# SCH_QLC_CONNECTOR_2023-04-06.net
KiCad netlist of a schematic drawn in EasyEDA
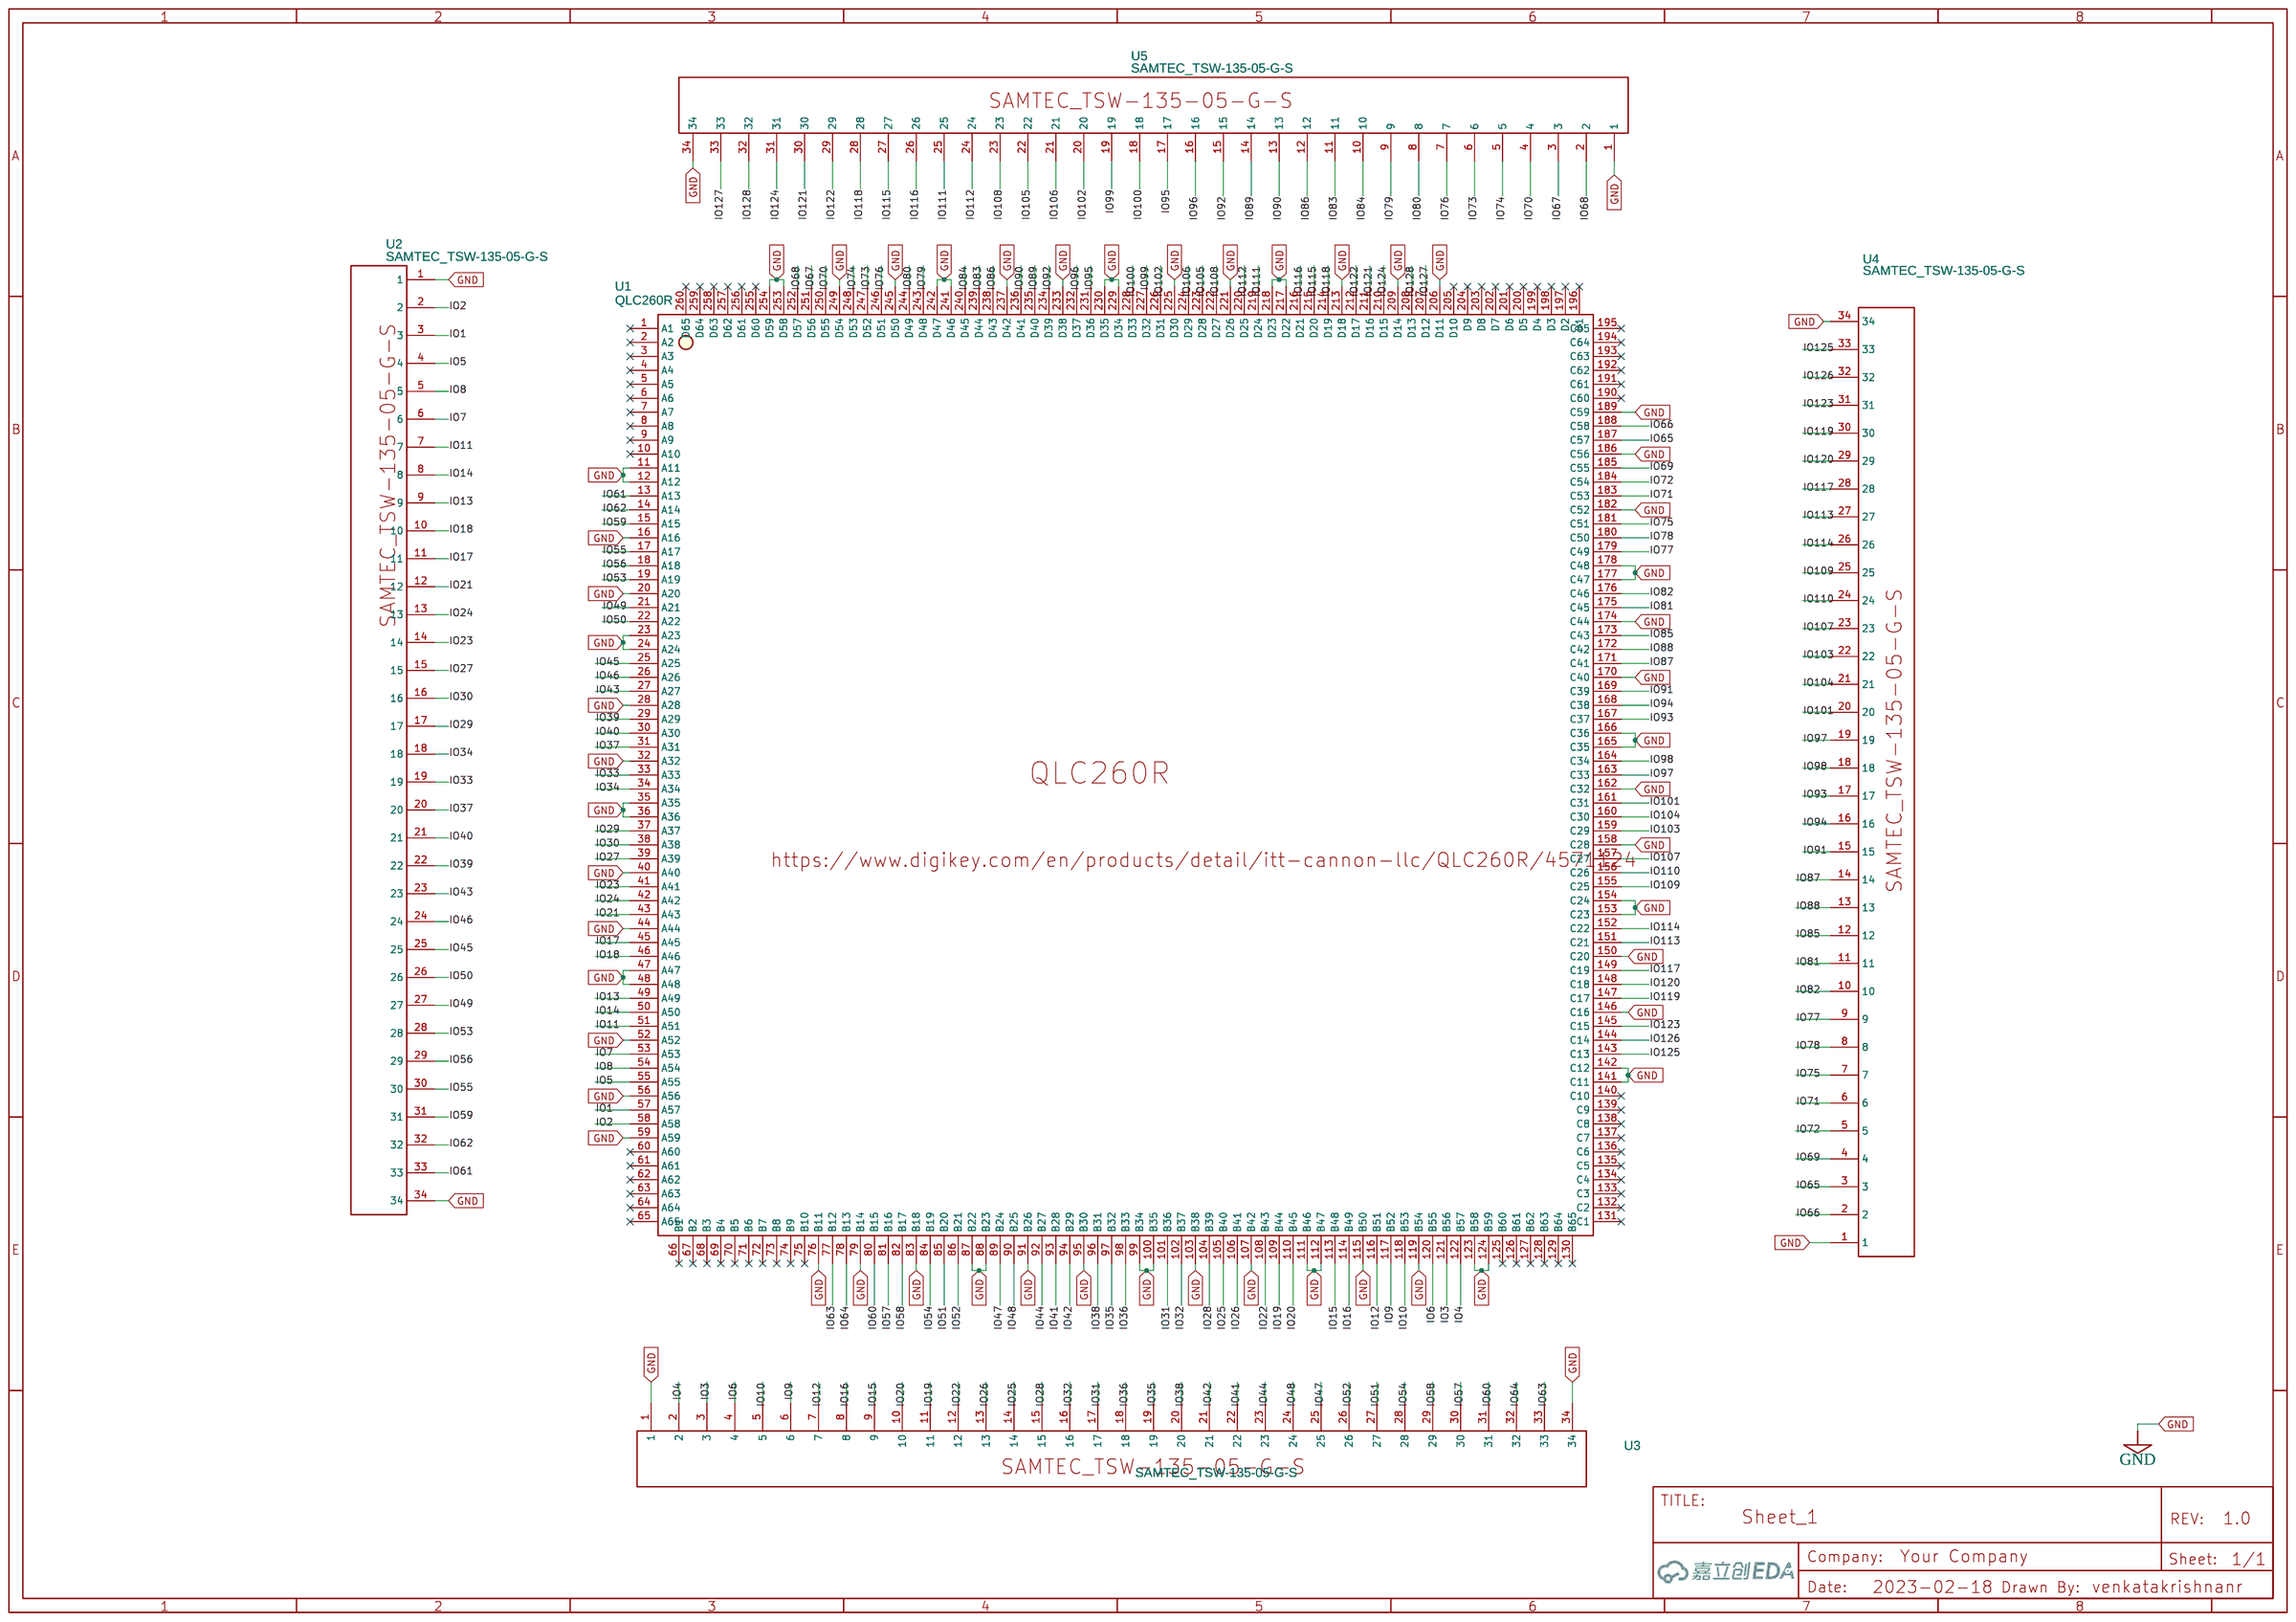
[diagram p0: schematic sheet]

(export (version "E")
  (design (tool "Eeschema 10.0.6"))
  (components
    (comp (ref "U1")
      (value "QLC260R")
      (fields (field (name "BOM_Supplier Part") "1003-2400-ND"))
      (libsource (lib "") (part "QLC260R"))
    )
    (comp (ref "U2")
      (value "SAMTEC_TSW-135-05-G-S")
      (fields
        (field (name "BOM_Manufacturer Part") "TSW-135-05-G-S")
        (field (name "BOM_Supplier Part") "SAM1013-35-ND")
      )
      (libsource (lib "") (part "SAMTEC_TSW-135-05-G-S_1"))
    )
    (comp (ref "U3")
      (value "SAMTEC_TSW-135-05-G-S")
      (fields
        (field (name "BOM_Manufacturer Part") "TSW-135-05-G-S")
        (field (name "BOM_Supplier Part") "SAM1013-35-ND")
      )
      (libsource (lib "") (part "SAMTEC_TSW-135-05-G-S"))
    )
    (comp (ref "U4")
      (value "SAMTEC_TSW-135-05-G-S")
      (fields
        (field (name "BOM_Manufacturer Part") "TSW-135-05-G-S")
        (field (name "BOM_Supplier Part") "SAM1013-35-ND")
      )
      (libsource (lib "") (part "SAMTEC_TSW-135-05-G-S_2"))
    )
    (comp (ref "U5")
      (value "SAMTEC_TSW-135-05-G-S")
      (fields
        (field (name "BOM_Manufacturer Part") "TSW-135-05-G-S")
        (field (name "BOM_Supplier Part") "SAM1013-35-ND")
      )
      (libsource (lib "") (part "SAMTEC_TSW-135-05-G-S_3"))
    )
  )
  (nets
    (net (code "1") (name "/IO1") (class "Default")
      (node (ref "U1") (pin "57") (pinfunction "A57_57") (pintype "unspecified"))
      (node (ref "U2") (pin "3") (pinfunction "3_3") (pintype "unspecified"))
    )
    (net (code "2") (name "/IO2") (class "Default")
      (node (ref "U1") (pin "58") (pinfunction "A58_58") (pintype "unspecified"))
      (node (ref "U2") (pin "2") (pinfunction "2_2") (pintype "unspecified"))
    )
    (net (code "3") (name "/IO3") (class "Default")
      (node (ref "U1") (pin "121") (pinfunction "B56_121") (pintype "unspecified"))
      (node (ref "U3") (pin "3") (pinfunction "3_3") (pintype "unspecified"))
    )
    (net (code "4") (name "/IO4") (class "Default")
      (node (ref "U1") (pin "122") (pinfunction "B57_122") (pintype "unspecified"))
      (node (ref "U3") (pin "2") (pinfunction "2_2") (pintype "unspecified"))
    )
    (net (code "5") (name "/IO5") (class "Default")
      (node (ref "U1") (pin "55") (pinfunction "A55_55") (pintype "unspecified"))
      (node (ref "U2") (pin "4") (pinfunction "4_4") (pintype "unspecified"))
    )
    (net (code "6") (name "/IO6") (class "Default")
      (node (ref "U1") (pin "120") (pinfunction "B55_120") (pintype "unspecified"))
      (node (ref "U3") (pin "4") (pinfunction "4_4") (pintype "unspecified"))
    )
    (net (code "7") (name "/IO7") (class "Default")
      (node (ref "U1") (pin "53") (pinfunction "A53_53") (pintype "unspecified"))
      (node (ref "U2") (pin "6") (pinfunction "6_6") (pintype "unspecified"))
    )
    (net (code "8") (name "/IO8") (class "Default")
      (node (ref "U1") (pin "54") (pinfunction "A54_54") (pintype "unspecified"))
      (node (ref "U2") (pin "5") (pinfunction "5_5") (pintype "unspecified"))
    )
    (net (code "9") (name "/IO9") (class "Default")
      (node (ref "U1") (pin "117") (pinfunction "B52_117") (pintype "unspecified"))
      (node (ref "U3") (pin "6") (pinfunction "6_6") (pintype "unspecified"))
    )
    (net (code "10") (name "/IO10") (class "Default")
      (node (ref "U1") (pin "118") (pinfunction "B53_118") (pintype "unspecified"))
      (node (ref "U3") (pin "5") (pinfunction "5_5") (pintype "unspecified"))
    )
    (net (code "11") (name "/IO11") (class "Default")
      (node (ref "U1") (pin "51") (pinfunction "A51_51") (pintype "unspecified"))
      (node (ref "U2") (pin "7") (pinfunction "7_7") (pintype "unspecified"))
    )
    (net (code "12") (name "/IO12") (class "Default")
      (node (ref "U1") (pin "116") (pinfunction "B51_116") (pintype "unspecified"))
      (node (ref "U3") (pin "7") (pinfunction "7_7") (pintype "unspecified"))
    )
    (net (code "13") (name "/IO13") (class "Default")
      (node (ref "U1") (pin "49") (pinfunction "A49_49") (pintype "unspecified"))
      (node (ref "U2") (pin "9") (pinfunction "9_9") (pintype "unspecified"))
    )
    (net (code "14") (name "/IO14") (class "Default")
      (node (ref "U1") (pin "50") (pinfunction "A50_50") (pintype "unspecified"))
      (node (ref "U2") (pin "8") (pinfunction "8_8") (pintype "unspecified"))
    )
    (net (code "15") (name "/IO15") (class "Default")
      (node (ref "U1") (pin "113") (pinfunction "B48_113") (pintype "unspecified"))
      (node (ref "U3") (pin "9") (pinfunction "9_9") (pintype "unspecified"))
    )
    (net (code "16") (name "/IO16") (class "Default")
      (node (ref "U1") (pin "114") (pinfunction "B49_114") (pintype "unspecified"))
      (node (ref "U3") (pin "8") (pinfunction "8_8") (pintype "unspecified"))
    )
    (net (code "17") (name "/IO17") (class "Default")
      (node (ref "U1") (pin "45") (pinfunction "A45_45") (pintype "unspecified"))
      (node (ref "U2") (pin "11") (pinfunction "11_11") (pintype "unspecified"))
    )
    (net (code "18") (name "/IO18") (class "Default")
      (node (ref "U1") (pin "46") (pinfunction "A46_46") (pintype "unspecified"))
      (node (ref "U2") (pin "10") (pinfunction "10_10") (pintype "unspecified"))
    )
    (net (code "19") (name "/IO19") (class "Default")
      (node (ref "U1") (pin "109") (pinfunction "B44_109") (pintype "unspecified"))
      (node (ref "U3") (pin "11") (pinfunction "11_11") (pintype "unspecified"))
    )
    (net (code "20") (name "/IO20") (class "Default")
      (node (ref "U1") (pin "110") (pinfunction "B45_110") (pintype "unspecified"))
      (node (ref "U3") (pin "10") (pinfunction "10_10") (pintype "unspecified"))
    )
    (net (code "21") (name "/IO21") (class "Default")
      (node (ref "U1") (pin "43") (pinfunction "A43_43") (pintype "unspecified"))
      (node (ref "U2") (pin "12") (pinfunction "12_12") (pintype "unspecified"))
    )
    (net (code "22") (name "/IO22") (class "Default")
      (node (ref "U1") (pin "108") (pinfunction "B43_108") (pintype "unspecified"))
      (node (ref "U3") (pin "12") (pinfunction "12_12") (pintype "unspecified"))
    )
    (net (code "23") (name "/IO23") (class "Default")
      (node (ref "U1") (pin "41") (pinfunction "A41_41") (pintype "unspecified"))
      (node (ref "U2") (pin "14") (pinfunction "14_14") (pintype "unspecified"))
    )
    (net (code "24") (name "/IO24") (class "Default")
      (node (ref "U1") (pin "42") (pinfunction "A42_42") (pintype "unspecified"))
      (node (ref "U2") (pin "13") (pinfunction "13_13") (pintype "unspecified"))
    )
    (net (code "25") (name "/IO25") (class "Default")
      (node (ref "U1") (pin "105") (pinfunction "B40_105") (pintype "unspecified"))
      (node (ref "U3") (pin "14") (pinfunction "14_14") (pintype "unspecified"))
    )
    (net (code "26") (name "/IO26") (class "Default")
      (node (ref "U1") (pin "106") (pinfunction "B41_106") (pintype "unspecified"))
      (node (ref "U3") (pin "13") (pinfunction "13_13") (pintype "unspecified"))
    )
    (net (code "27") (name "/IO27") (class "Default")
      (node (ref "U1") (pin "39") (pinfunction "A39_39") (pintype "unspecified"))
      (node (ref "U2") (pin "15") (pinfunction "15_15") (pintype "unspecified"))
    )
    (net (code "28") (name "/IO28") (class "Default")
      (node (ref "U1") (pin "104") (pinfunction "B39_104") (pintype "unspecified"))
      (node (ref "U3") (pin "15") (pinfunction "15_15") (pintype "unspecified"))
    )
    (net (code "29") (name "/IO29") (class "Default")
      (node (ref "U1") (pin "37") (pinfunction "A37_37") (pintype "unspecified"))
      (node (ref "U2") (pin "17") (pinfunction "17_17") (pintype "unspecified"))
    )
    (net (code "30") (name "/IO30") (class "Default")
      (node (ref "U1") (pin "38") (pinfunction "A38_38") (pintype "unspecified"))
      (node (ref "U2") (pin "16") (pinfunction "16_16") (pintype "unspecified"))
    )
    (net (code "31") (name "/IO31") (class "Default")
      (node (ref "U1") (pin "101") (pinfunction "B36_101") (pintype "unspecified"))
      (node (ref "U3") (pin "17") (pinfunction "17_17") (pintype "unspecified"))
    )
    (net (code "32") (name "/IO32") (class "Default")
      (node (ref "U1") (pin "102") (pinfunction "B37_102") (pintype "unspecified"))
      (node (ref "U3") (pin "16") (pinfunction "16_16") (pintype "unspecified"))
    )
    (net (code "33") (name "/IO33") (class "Default")
      (node (ref "U1") (pin "33") (pinfunction "A33_33") (pintype "unspecified"))
      (node (ref "U2") (pin "19") (pinfunction "19_19") (pintype "unspecified"))
    )
    (net (code "34") (name "/IO34") (class "Default")
      (node (ref "U1") (pin "34") (pinfunction "A34_34") (pintype "unspecified"))
      (node (ref "U2") (pin "18") (pinfunction "18_18") (pintype "unspecified"))
    )
    (net (code "35") (name "/IO35") (class "Default")
      (node (ref "U1") (pin "97") (pinfunction "B32_97") (pintype "unspecified"))
      (node (ref "U3") (pin "19") (pinfunction "19_19") (pintype "unspecified"))
    )
    (net (code "36") (name "/IO36") (class "Default")
      (node (ref "U1") (pin "98") (pinfunction "B33_98") (pintype "unspecified"))
      (node (ref "U3") (pin "18") (pinfunction "18_18") (pintype "unspecified"))
    )
    (net (code "37") (name "/IO37") (class "Default")
      (node (ref "U1") (pin "31") (pinfunction "A31_31") (pintype "unspecified"))
      (node (ref "U2") (pin "20") (pinfunction "20_20") (pintype "unspecified"))
    )
    (net (code "38") (name "/IO38") (class "Default")
      (node (ref "U1") (pin "96") (pinfunction "B31_96") (pintype "unspecified"))
      (node (ref "U3") (pin "20") (pinfunction "20_20") (pintype "unspecified"))
    )
    (net (code "39") (name "/IO39") (class "Default")
      (node (ref "U1") (pin "29") (pinfunction "A29_29") (pintype "unspecified"))
      (node (ref "U2") (pin "22") (pinfunction "22_22") (pintype "unspecified"))
    )
    (net (code "40") (name "/IO40") (class "Default")
      (node (ref "U1") (pin "30") (pinfunction "A30_30") (pintype "unspecified"))
      (node (ref "U2") (pin "21") (pinfunction "21_21") (pintype "unspecified"))
    )
    (net (code "41") (name "/IO41") (class "Default")
      (node (ref "U1") (pin "93") (pinfunction "B28_93") (pintype "unspecified"))
      (node (ref "U3") (pin "22") (pinfunction "22_22") (pintype "unspecified"))
    )
    (net (code "42") (name "/IO42") (class "Default")
      (node (ref "U1") (pin "94") (pinfunction "B29_94") (pintype "unspecified"))
      (node (ref "U3") (pin "21") (pinfunction "21_21") (pintype "unspecified"))
    )
    (net (code "43") (name "/IO43") (class "Default")
      (node (ref "U1") (pin "27") (pinfunction "A27_27") (pintype "unspecified"))
      (node (ref "U2") (pin "23") (pinfunction "23_23") (pintype "unspecified"))
    )
    (net (code "44") (name "/IO44") (class "Default")
      (node (ref "U1") (pin "92") (pinfunction "B27_92") (pintype "unspecified"))
      (node (ref "U3") (pin "23") (pinfunction "23_23") (pintype "unspecified"))
    )
    (net (code "45") (name "/IO45") (class "Default")
      (node (ref "U1") (pin "25") (pinfunction "A25_25") (pintype "unspecified"))
      (node (ref "U2") (pin "25") (pinfunction "25_25") (pintype "unspecified"))
    )
    (net (code "46") (name "/IO46") (class "Default")
      (node (ref "U1") (pin "26") (pinfunction "A26_26") (pintype "unspecified"))
      (node (ref "U2") (pin "24") (pinfunction "24_24") (pintype "unspecified"))
    )
    (net (code "47") (name "/IO47") (class "Default")
      (node (ref "U1") (pin "89") (pinfunction "B24_89") (pintype "unspecified"))
      (node (ref "U3") (pin "25") (pinfunction "25_25") (pintype "unspecified"))
    )
    (net (code "48") (name "/IO48") (class "Default")
      (node (ref "U1") (pin "90") (pinfunction "B25_90") (pintype "unspecified"))
      (node (ref "U3") (pin "24") (pinfunction "24_24") (pintype "unspecified"))
    )
    (net (code "49") (name "/IO49") (class "Default")
      (node (ref "U1") (pin "21") (pinfunction "A21_21") (pintype "unspecified"))
      (node (ref "U2") (pin "27") (pinfunction "27_27") (pintype "unspecified"))
    )
    (net (code "50") (name "/IO50") (class "Default")
      (node (ref "U1") (pin "22") (pinfunction "A22_22") (pintype "unspecified"))
      (node (ref "U2") (pin "26") (pinfunction "26_26") (pintype "unspecified"))
    )
    (net (code "51") (name "/IO51") (class "Default")
      (node (ref "U1") (pin "85") (pinfunction "B20_85") (pintype "unspecified"))
      (node (ref "U3") (pin "27") (pinfunction "27_27") (pintype "unspecified"))
    )
    (net (code "52") (name "/IO52") (class "Default")
      (node (ref "U1") (pin "86") (pinfunction "B21_86") (pintype "unspecified"))
      (node (ref "U3") (pin "26") (pinfunction "26_26") (pintype "unspecified"))
    )
    (net (code "53") (name "/IO53") (class "Default")
      (node (ref "U1") (pin "19") (pinfunction "A19_19") (pintype "unspecified"))
      (node (ref "U2") (pin "28") (pinfunction "28_28") (pintype "unspecified"))
    )
    (net (code "54") (name "/IO54") (class "Default")
      (node (ref "U1") (pin "84") (pinfunction "B19_84") (pintype "unspecified"))
      (node (ref "U3") (pin "28") (pinfunction "28_28") (pintype "unspecified"))
    )
    (net (code "55") (name "/IO55") (class "Default")
      (node (ref "U1") (pin "17") (pinfunction "A17_17") (pintype "unspecified"))
      (node (ref "U2") (pin "30") (pinfunction "30_30") (pintype "unspecified"))
    )
    (net (code "56") (name "/IO56") (class "Default")
      (node (ref "U1") (pin "18") (pinfunction "A18_18") (pintype "unspecified"))
      (node (ref "U2") (pin "29") (pinfunction "29_29") (pintype "unspecified"))
    )
    (net (code "57") (name "/IO57") (class "Default")
      (node (ref "U1") (pin "81") (pinfunction "B16_81") (pintype "unspecified"))
      (node (ref "U3") (pin "30") (pinfunction "30_30") (pintype "unspecified"))
    )
    (net (code "58") (name "/IO58") (class "Default")
      (node (ref "U1") (pin "82") (pinfunction "B17_82") (pintype "unspecified"))
      (node (ref "U3") (pin "29") (pinfunction "29_29") (pintype "unspecified"))
    )
    (net (code "59") (name "/IO59") (class "Default")
      (node (ref "U1") (pin "15") (pinfunction "A15_15") (pintype "unspecified"))
      (node (ref "U2") (pin "31") (pinfunction "31_31") (pintype "unspecified"))
    )
    (net (code "60") (name "/IO60") (class "Default")
      (node (ref "U1") (pin "80") (pinfunction "B15_80") (pintype "unspecified"))
      (node (ref "U3") (pin "31") (pinfunction "31_31") (pintype "unspecified"))
    )
    (net (code "61") (name "/IO61") (class "Default")
      (node (ref "U1") (pin "13") (pinfunction "A13_13") (pintype "unspecified"))
      (node (ref "U2") (pin "33") (pinfunction "33_33") (pintype "unspecified"))
    )
    (net (code "62") (name "/IO62") (class "Default")
      (node (ref "U1") (pin "14") (pinfunction "A14_14") (pintype "unspecified"))
      (node (ref "U2") (pin "32") (pinfunction "32_32") (pintype "unspecified"))
    )
    (net (code "63") (name "/IO63") (class "Default")
      (node (ref "U1") (pin "77") (pinfunction "B12_77") (pintype "unspecified"))
      (node (ref "U3") (pin "33") (pinfunction "33_33") (pintype "unspecified"))
    )
    (net (code "64") (name "/IO64") (class "Default")
      (node (ref "U1") (pin "78") (pinfunction "B13_78") (pintype "unspecified"))
      (node (ref "U3") (pin "32") (pinfunction "32_32") (pintype "unspecified"))
    )
    (net (code "65") (name "/IO65") (class "Default")
      (node (ref "U1") (pin "187") (pinfunction "C57_187") (pintype "unspecified"))
      (node (ref "U4") (pin "3") (pinfunction "3_3") (pintype "unspecified"))
    )
    (net (code "66") (name "/IO66") (class "Default")
      (node (ref "U1") (pin "188") (pinfunction "C58_188") (pintype "unspecified"))
      (node (ref "U4") (pin "2") (pinfunction "2_2") (pintype "unspecified"))
    )
    (net (code "67") (name "/IO67") (class "Default")
      (node (ref "U1") (pin "251") (pinfunction "D56_251") (pintype "unspecified"))
      (node (ref "U5") (pin "3") (pinfunction "3_3") (pintype "unspecified"))
    )
    (net (code "68") (name "/IO68") (class "Default")
      (node (ref "U1") (pin "252") (pinfunction "D57_252") (pintype "unspecified"))
      (node (ref "U5") (pin "2") (pinfunction "2_2") (pintype "unspecified"))
    )
    (net (code "69") (name "/IO69") (class "Default")
      (node (ref "U1") (pin "185") (pinfunction "C55_185") (pintype "unspecified"))
      (node (ref "U4") (pin "4") (pinfunction "4_4") (pintype "unspecified"))
    )
    (net (code "70") (name "/IO70") (class "Default")
      (node (ref "U1") (pin "250") (pinfunction "D55_250") (pintype "unspecified"))
      (node (ref "U5") (pin "4") (pinfunction "4_4") (pintype "unspecified"))
    )
    (net (code "71") (name "/IO71") (class "Default")
      (node (ref "U1") (pin "183") (pinfunction "C53_183") (pintype "unspecified"))
      (node (ref "U4") (pin "6") (pinfunction "6_6") (pintype "unspecified"))
    )
    (net (code "72") (name "/IO72") (class "Default")
      (node (ref "U1") (pin "184") (pinfunction "C54_184") (pintype "unspecified"))
      (node (ref "U4") (pin "5") (pinfunction "5_5") (pintype "unspecified"))
    )
    (net (code "73") (name "/IO73") (class "Default")
      (node (ref "U1") (pin "247") (pinfunction "D52_247") (pintype "unspecified"))
      (node (ref "U5") (pin "6") (pinfunction "6_6") (pintype "unspecified"))
    )
    (net (code "74") (name "/IO74") (class "Default")
      (node (ref "U1") (pin "248") (pinfunction "D53_248") (pintype "unspecified"))
      (node (ref "U5") (pin "5") (pinfunction "5_5") (pintype "unspecified"))
    )
    (net (code "75") (name "/IO75") (class "Default")
      (node (ref "U1") (pin "181") (pinfunction "C51_181") (pintype "unspecified"))
      (node (ref "U4") (pin "7") (pinfunction "7_7") (pintype "unspecified"))
    )
    (net (code "76") (name "/IO76") (class "Default")
      (node (ref "U1") (pin "246") (pinfunction "D51_246") (pintype "unspecified"))
      (node (ref "U5") (pin "7") (pinfunction "7_7") (pintype "unspecified"))
    )
    (net (code "77") (name "/IO77") (class "Default")
      (node (ref "U1") (pin "179") (pinfunction "C49_179") (pintype "unspecified"))
      (node (ref "U4") (pin "9") (pinfunction "9_9") (pintype "unspecified"))
    )
    (net (code "78") (name "/IO78") (class "Default")
      (node (ref "U1") (pin "180") (pinfunction "C50_180") (pintype "unspecified"))
      (node (ref "U4") (pin "8") (pinfunction "8_8") (pintype "unspecified"))
    )
    (net (code "79") (name "/IO79") (class "Default")
      (node (ref "U1") (pin "243") (pinfunction "D48_243") (pintype "unspecified"))
      (node (ref "U5") (pin "9") (pinfunction "9_9") (pintype "unspecified"))
    )
    (net (code "80") (name "/IO80") (class "Default")
      (node (ref "U1") (pin "244") (pinfunction "D49_244") (pintype "unspecified"))
      (node (ref "U5") (pin "8") (pinfunction "8_8") (pintype "unspecified"))
    )
    (net (code "81") (name "/IO81") (class "Default")
      (node (ref "U1") (pin "175") (pinfunction "C45_175") (pintype "unspecified"))
      (node (ref "U4") (pin "11") (pinfunction "11_11") (pintype "unspecified"))
    )
    (net (code "82") (name "/IO82") (class "Default")
      (node (ref "U1") (pin "176") (pinfunction "C46_176") (pintype "unspecified"))
      (node (ref "U4") (pin "10") (pinfunction "10_10") (pintype "unspecified"))
    )
    (net (code "83") (name "/IO83") (class "Default")
      (node (ref "U1") (pin "239") (pinfunction "D44_239") (pintype "unspecified"))
      (node (ref "U5") (pin "11") (pinfunction "11_11") (pintype "unspecified"))
    )
    (net (code "84") (name "/IO84") (class "Default")
      (node (ref "U1") (pin "240") (pinfunction "D45_240") (pintype "unspecified"))
      (node (ref "U5") (pin "10") (pinfunction "10_10") (pintype "unspecified"))
    )
    (net (code "85") (name "/IO85") (class "Default")
      (node (ref "U1") (pin "173") (pinfunction "C43_173") (pintype "unspecified"))
      (node (ref "U4") (pin "12") (pinfunction "12_12") (pintype "unspecified"))
    )
    (net (code "86") (name "/IO86") (class "Default")
      (node (ref "U1") (pin "238") (pinfunction "D43_238") (pintype "unspecified"))
      (node (ref "U5") (pin "12") (pinfunction "12_12") (pintype "unspecified"))
    )
    (net (code "87") (name "/IO87") (class "Default")
      (node (ref "U1") (pin "171") (pinfunction "C41_171") (pintype "unspecified"))
      (node (ref "U4") (pin "14") (pinfunction "14_14") (pintype "unspecified"))
    )
    (net (code "88") (name "/IO88") (class "Default")
      (node (ref "U1") (pin "172") (pinfunction "C42_172") (pintype "unspecified"))
      (node (ref "U4") (pin "13") (pinfunction "13_13") (pintype "unspecified"))
    )
    (net (code "89") (name "/IO89") (class "Default")
      (node (ref "U1") (pin "235") (pinfunction "D40_235") (pintype "unspecified"))
      (node (ref "U5") (pin "14") (pinfunction "14_14") (pintype "unspecified"))
    )
    (net (code "90") (name "/IO90") (class "Default")
      (node (ref "U1") (pin "236") (pinfunction "D41_236") (pintype "unspecified"))
      (node (ref "U5") (pin "13") (pinfunction "13_13") (pintype "unspecified"))
    )
    (net (code "91") (name "/IO91") (class "Default")
      (node (ref "U1") (pin "169") (pinfunction "C39_169") (pintype "unspecified"))
      (node (ref "U4") (pin "15") (pinfunction "15_15") (pintype "unspecified"))
    )
    (net (code "92") (name "/IO92") (class "Default")
      (node (ref "U1") (pin "234") (pinfunction "D39_234") (pintype "unspecified"))
      (node (ref "U5") (pin "15") (pinfunction "15_15") (pintype "unspecified"))
    )
    (net (code "93") (name "/IO93") (class "Default")
      (node (ref "U1") (pin "167") (pinfunction "C37_167") (pintype "unspecified"))
      (node (ref "U4") (pin "17") (pinfunction "17_17") (pintype "unspecified"))
    )
    (net (code "94") (name "/IO94") (class "Default")
      (node (ref "U1") (pin "168") (pinfunction "C38_168") (pintype "unspecified"))
      (node (ref "U4") (pin "16") (pinfunction "16_16") (pintype "unspecified"))
    )
    (net (code "95") (name "/IO95") (class "Default")
      (node (ref "U1") (pin "231") (pinfunction "D36_231") (pintype "unspecified"))
      (node (ref "U5") (pin "17") (pinfunction "17_17") (pintype "unspecified"))
    )
    (net (code "96") (name "/IO96") (class "Default")
      (node (ref "U1") (pin "232") (pinfunction "D37_232") (pintype "unspecified"))
      (node (ref "U5") (pin "16") (pinfunction "16_16") (pintype "unspecified"))
    )
    (net (code "97") (name "/IO97") (class "Default")
      (node (ref "U1") (pin "163") (pinfunction "C33_163") (pintype "unspecified"))
      (node (ref "U4") (pin "19") (pinfunction "19_19") (pintype "unspecified"))
    )
    (net (code "98") (name "/IO98") (class "Default")
      (node (ref "U1") (pin "164") (pinfunction "C34_164") (pintype "unspecified"))
      (node (ref "U4") (pin "18") (pinfunction "18_18") (pintype "unspecified"))
    )
    (net (code "99") (name "/IO99") (class "Default")
      (node (ref "U1") (pin "227") (pinfunction "D32_227") (pintype "unspecified"))
      (node (ref "U5") (pin "19") (pinfunction "19_19") (pintype "unspecified"))
    )
    (net (code "100") (name "/IO100") (class "Default")
      (node (ref "U1") (pin "228") (pinfunction "D33_228") (pintype "unspecified"))
      (node (ref "U5") (pin "18") (pinfunction "18_18") (pintype "unspecified"))
    )
    (net (code "101") (name "/IO101") (class "Default")
      (node (ref "U1") (pin "161") (pinfunction "C31_161") (pintype "unspecified"))
      (node (ref "U4") (pin "20") (pinfunction "20_20") (pintype "unspecified"))
    )
    (net (code "102") (name "/IO102") (class "Default")
      (node (ref "U1") (pin "226") (pinfunction "D31_226") (pintype "unspecified"))
      (node (ref "U5") (pin "20") (pinfunction "20_20") (pintype "unspecified"))
    )
    (net (code "103") (name "/IO103") (class "Default")
      (node (ref "U1") (pin "159") (pinfunction "C29_159") (pintype "unspecified"))
      (node (ref "U4") (pin "22") (pinfunction "22_22") (pintype "unspecified"))
    )
    (net (code "104") (name "/IO104") (class "Default")
      (node (ref "U1") (pin "160") (pinfunction "C30_160") (pintype "unspecified"))
      (node (ref "U4") (pin "21") (pinfunction "21_21") (pintype "unspecified"))
    )
    (net (code "105") (name "/IO105") (class "Default")
      (node (ref "U1") (pin "223") (pinfunction "D28_223") (pintype "unspecified"))
      (node (ref "U5") (pin "22") (pinfunction "22_22") (pintype "unspecified"))
    )
    (net (code "106") (name "/IO106") (class "Default")
      (node (ref "U1") (pin "224") (pinfunction "D29_224") (pintype "unspecified"))
      (node (ref "U5") (pin "21") (pinfunction "21_21") (pintype "unspecified"))
    )
    (net (code "107") (name "/IO107") (class "Default")
      (node (ref "U1") (pin "157") (pinfunction "C27_157") (pintype "unspecified"))
      (node (ref "U4") (pin "23") (pinfunction "23_23") (pintype "unspecified"))
    )
    (net (code "108") (name "/IO108") (class "Default")
      (node (ref "U1") (pin "222") (pinfunction "D27_222") (pintype "unspecified"))
      (node (ref "U5") (pin "23") (pinfunction "23_23") (pintype "unspecified"))
    )
    (net (code "109") (name "/IO109") (class "Default")
      (node (ref "U1") (pin "155") (pinfunction "C25_155") (pintype "unspecified"))
      (node (ref "U4") (pin "25") (pinfunction "25_25") (pintype "unspecified"))
    )
    (net (code "110") (name "/IO110") (class "Default")
      (node (ref "U1") (pin "156") (pinfunction "C26_156") (pintype "unspecified"))
      (node (ref "U4") (pin "24") (pinfunction "24_24") (pintype "unspecified"))
    )
    (net (code "111") (name "/IO111") (class "Default")
      (node (ref "U1") (pin "219") (pinfunction "D24_219") (pintype "unspecified"))
      (node (ref "U5") (pin "25") (pinfunction "25_25") (pintype "unspecified"))
    )
    (net (code "112") (name "/IO112") (class "Default")
      (node (ref "U1") (pin "220") (pinfunction "D25_220") (pintype "unspecified"))
      (node (ref "U5") (pin "24") (pinfunction "24_24") (pintype "unspecified"))
    )
    (net (code "113") (name "/IO113") (class "Default")
      (node (ref "U1") (pin "151") (pinfunction "C21_151") (pintype "unspecified"))
      (node (ref "U4") (pin "27") (pinfunction "27_27") (pintype "unspecified"))
    )
    (net (code "114") (name "/IO114") (class "Default")
      (node (ref "U1") (pin "152") (pinfunction "C22_152") (pintype "unspecified"))
      (node (ref "U4") (pin "26") (pinfunction "26_26") (pintype "unspecified"))
    )
    (net (code "115") (name "/IO115") (class "Default")
      (node (ref "U1") (pin "215") (pinfunction "D20_215") (pintype "unspecified"))
      (node (ref "U5") (pin "27") (pinfunction "27_27") (pintype "unspecified"))
    )
    (net (code "116") (name "/IO116") (class "Default")
      (node (ref "U1") (pin "216") (pinfunction "D21_216") (pintype "unspecified"))
      (node (ref "U5") (pin "26") (pinfunction "26_26") (pintype "unspecified"))
    )
    (net (code "117") (name "/IO117") (class "Default")
      (node (ref "U1") (pin "149") (pinfunction "C19_149") (pintype "unspecified"))
      (node (ref "U4") (pin "28") (pinfunction "28_28") (pintype "unspecified"))
    )
    (net (code "118") (name "/IO118") (class "Default")
      (node (ref "U1") (pin "214") (pinfunction "D19_214") (pintype "unspecified"))
      (node (ref "U5") (pin "28") (pinfunction "28_28") (pintype "unspecified"))
    )
    (net (code "119") (name "/IO119") (class "Default")
      (node (ref "U1") (pin "147") (pinfunction "C17_147") (pintype "unspecified"))
      (node (ref "U4") (pin "30") (pinfunction "30_30") (pintype "unspecified"))
    )
    (net (code "120") (name "/IO120") (class "Default")
      (node (ref "U1") (pin "148") (pinfunction "C18_148") (pintype "unspecified"))
      (node (ref "U4") (pin "29") (pinfunction "29_29") (pintype "unspecified"))
    )
    (net (code "121") (name "/IO121") (class "Default")
      (node (ref "U1") (pin "211") (pinfunction "D16_211") (pintype "unspecified"))
      (node (ref "U5") (pin "30") (pinfunction "30_30") (pintype "unspecified"))
    )
    (net (code "122") (name "/IO122") (class "Default")
      (node (ref "U1") (pin "212") (pinfunction "D17_212") (pintype "unspecified"))
      (node (ref "U5") (pin "29") (pinfunction "29_29") (pintype "unspecified"))
    )
    (net (code "123") (name "/IO123") (class "Default")
      (node (ref "U1") (pin "145") (pinfunction "C15_145") (pintype "unspecified"))
      (node (ref "U4") (pin "31") (pinfunction "31_31") (pintype "unspecified"))
    )
    (net (code "124") (name "/IO124") (class "Default")
      (node (ref "U1") (pin "210") (pinfunction "D15_210") (pintype "unspecified"))
      (node (ref "U5") (pin "31") (pinfunction "31_31") (pintype "unspecified"))
    )
    (net (code "125") (name "/IO125") (class "Default")
      (node (ref "U1") (pin "143") (pinfunction "C13_143") (pintype "unspecified"))
      (node (ref "U4") (pin "33") (pinfunction "33_33") (pintype "unspecified"))
    )
    (net (code "126") (name "/IO126") (class "Default")
      (node (ref "U1") (pin "144") (pinfunction "C14_144") (pintype "unspecified"))
      (node (ref "U4") (pin "32") (pinfunction "32_32") (pintype "unspecified"))
    )
    (net (code "127") (name "/IO127") (class "Default")
      (node (ref "U1") (pin "207") (pinfunction "D12_207") (pintype "unspecified"))
      (node (ref "U5") (pin "33") (pinfunction "33_33") (pintype "unspecified"))
    )
    (net (code "128") (name "/IO128") (class "Default")
      (node (ref "U1") (pin "208") (pinfunction "D13_208") (pintype "unspecified"))
      (node (ref "U5") (pin "32") (pinfunction "32_32") (pintype "unspecified"))
    )
    (net (code "129") (name "GND") (class "Default")
      (node (ref "U1") (pin "100") (pinfunction "B35_100") (pintype "unspecified"))
      (node (ref "U1") (pin "103") (pinfunction "B38_103") (pintype "unspecified"))
      (node (ref "U1") (pin "107") (pinfunction "B42_107") (pintype "unspecified"))
      (node (ref "U1") (pin "11") (pinfunction "A11_11") (pintype "unspecified"))
      (node (ref "U1") (pin "111") (pinfunction "B46_111") (pintype "unspecified"))
      (node (ref "U1") (pin "112") (pinfunction "B47_112") (pintype "unspecified"))
      (node (ref "U1") (pin "115") (pinfunction "B50_115") (pintype "unspecified"))
      (node (ref "U1") (pin "119") (pinfunction "B54_119") (pintype "unspecified"))
      (node (ref "U1") (pin "12") (pinfunction "A12_12") (pintype "unspecified"))
      (node (ref "U1") (pin "123") (pinfunction "B58_123") (pintype "unspecified"))
      (node (ref "U1") (pin "124") (pinfunction "B59_124") (pintype "unspecified"))
      (node (ref "U1") (pin "141") (pinfunction "C11_141") (pintype "unspecified"))
      (node (ref "U1") (pin "142") (pinfunction "C12_142") (pintype "unspecified"))
      (node (ref "U1") (pin "146") (pinfunction "C16_146") (pintype "unspecified"))
      (node (ref "U1") (pin "150") (pinfunction "C20_150") (pintype "unspecified"))
      (node (ref "U1") (pin "153") (pinfunction "C23_153") (pintype "unspecified"))
      (node (ref "U1") (pin "154") (pinfunction "C24_154") (pintype "unspecified"))
      (node (ref "U1") (pin "158") (pinfunction "C28_158") (pintype "unspecified"))
      (node (ref "U1") (pin "16") (pinfunction "A16_16") (pintype "unspecified"))
      (node (ref "U1") (pin "162") (pinfunction "C32_162") (pintype "unspecified"))
      (node (ref "U1") (pin "165") (pinfunction "C35_165") (pintype "unspecified"))
      (node (ref "U1") (pin "166") (pinfunction "C36_166") (pintype "unspecified"))
      (node (ref "U1") (pin "170") (pinfunction "C40_170") (pintype "unspecified"))
      (node (ref "U1") (pin "174") (pinfunction "C44_174") (pintype "unspecified"))
      (node (ref "U1") (pin "177") (pinfunction "C47_177") (pintype "unspecified"))
      (node (ref "U1") (pin "178") (pinfunction "C48_178") (pintype "unspecified"))
      (node (ref "U1") (pin "182") (pinfunction "C52_182") (pintype "unspecified"))
      (node (ref "U1") (pin "186") (pinfunction "C56_186") (pintype "unspecified"))
      (node (ref "U1") (pin "189") (pinfunction "C59_189") (pintype "unspecified"))
      (node (ref "U1") (pin "20") (pinfunction "A20_20") (pintype "unspecified"))
      (node (ref "U1") (pin "206") (pinfunction "D11_206") (pintype "unspecified"))
      (node (ref "U1") (pin "209") (pinfunction "D14_209") (pintype "unspecified"))
      (node (ref "U1") (pin "213") (pinfunction "D18_213") (pintype "unspecified"))
      (node (ref "U1") (pin "217") (pinfunction "D22_217") (pintype "unspecified"))
      (node (ref "U1") (pin "218") (pinfunction "D23_218") (pintype "unspecified"))
      (node (ref "U1") (pin "221") (pinfunction "D26_221") (pintype "unspecified"))
      (node (ref "U1") (pin "225") (pinfunction "D30_225") (pintype "unspecified"))
      (node (ref "U1") (pin "229") (pinfunction "D34_229") (pintype "unspecified"))
      (node (ref "U1") (pin "23") (pinfunction "A23_23") (pintype "unspecified"))
      (node (ref "U1") (pin "230") (pinfunction "D35_230") (pintype "unspecified"))
      (node (ref "U1") (pin "233") (pinfunction "D38_233") (pintype "unspecified"))
      (node (ref "U1") (pin "237") (pinfunction "D42_237") (pintype "unspecified"))
      (node (ref "U1") (pin "24") (pinfunction "A24_24") (pintype "unspecified"))
      (node (ref "U1") (pin "241") (pinfunction "D46_241") (pintype "unspecified"))
      (node (ref "U1") (pin "242") (pinfunction "D47_242") (pintype "unspecified"))
      (node (ref "U1") (pin "245") (pinfunction "D50_245") (pintype "unspecified"))
      (node (ref "U1") (pin "249") (pinfunction "D54_249") (pintype "unspecified"))
      (node (ref "U1") (pin "253") (pinfunction "D58_253") (pintype "unspecified"))
      (node (ref "U1") (pin "254") (pinfunction "D59_254") (pintype "unspecified"))
      (node (ref "U1") (pin "28") (pinfunction "A28_28") (pintype "unspecified"))
      (node (ref "U1") (pin "32") (pinfunction "A32_32") (pintype "unspecified"))
      (node (ref "U1") (pin "35") (pinfunction "A35_35") (pintype "unspecified"))
      (node (ref "U1") (pin "36") (pinfunction "A36_36") (pintype "unspecified"))
      (node (ref "U1") (pin "40") (pinfunction "A40_40") (pintype "unspecified"))
      (node (ref "U1") (pin "44") (pinfunction "A44_44") (pintype "unspecified"))
      (node (ref "U1") (pin "47") (pinfunction "A47_47") (pintype "unspecified"))
      (node (ref "U1") (pin "48") (pinfunction "A48_48") (pintype "unspecified"))
      (node (ref "U1") (pin "52") (pinfunction "A52_52") (pintype "unspecified"))
      (node (ref "U1") (pin "56") (pinfunction "A56_56") (pintype "unspecified"))
      (node (ref "U1") (pin "59") (pinfunction "A59_59") (pintype "unspecified"))
      (node (ref "U1") (pin "76") (pinfunction "B11_76") (pintype "unspecified"))
      (node (ref "U1") (pin "79") (pinfunction "B14_79") (pintype "unspecified"))
      (node (ref "U1") (pin "83") (pinfunction "B18_83") (pintype "unspecified"))
      (node (ref "U1") (pin "87") (pinfunction "B22_87") (pintype "unspecified"))
      (node (ref "U1") (pin "88") (pinfunction "B23_88") (pintype "unspecified"))
      (node (ref "U1") (pin "91") (pinfunction "B26_91") (pintype "unspecified"))
      (node (ref "U1") (pin "95") (pinfunction "B30_95") (pintype "unspecified"))
      (node (ref "U1") (pin "99") (pinfunction "B34_99") (pintype "unspecified"))
      (node (ref "U2") (pin "1") (pinfunction "1_1") (pintype "unspecified"))
      (node (ref "U2") (pin "34") (pinfunction "34_34") (pintype "unspecified"))
      (node (ref "U3") (pin "1") (pinfunction "1_1") (pintype "unspecified"))
      (node (ref "U3") (pin "34") (pinfunction "34_34") (pintype "unspecified"))
      (node (ref "U4") (pin "1") (pinfunction "1_1") (pintype "unspecified"))
      (node (ref "U4") (pin "34") (pinfunction "34_34") (pintype "unspecified"))
      (node (ref "U5") (pin "1") (pinfunction "1_1") (pintype "unspecified"))
      (node (ref "U5") (pin "34") (pinfunction "34_34") (pintype "unspecified"))
    )
    (net (code "130") (name "unconnected-(U1-A1-Pad1)") (class "Default")
      (node (ref "U1") (pin "1") (pinfunction "A1_1") (pintype "unspecified+no_connect"))
    )
    (net (code "131") (name "unconnected-(U1-A2-Pad2)") (class "Default")
      (node (ref "U1") (pin "2") (pinfunction "A2_2") (pintype "unspecified+no_connect"))
    )
    (net (code "132") (name "unconnected-(U1-A3-Pad3)") (class "Default")
      (node (ref "U1") (pin "3") (pinfunction "A3_3") (pintype "unspecified+no_connect"))
    )
    (net (code "133") (name "unconnected-(U1-A4-Pad4)") (class "Default")
      (node (ref "U1") (pin "4") (pinfunction "A4_4") (pintype "unspecified+no_connect"))
    )
    (net (code "134") (name "unconnected-(U1-A5-Pad5)") (class "Default")
      (node (ref "U1") (pin "5") (pinfunction "A5_5") (pintype "unspecified+no_connect"))
    )
    (net (code "135") (name "unconnected-(U1-A6-Pad6)") (class "Default")
      (node (ref "U1") (pin "6") (pinfunction "A6_6") (pintype "unspecified+no_connect"))
    )
    (net (code "136") (name "unconnected-(U1-A7-Pad7)") (class "Default")
      (node (ref "U1") (pin "7") (pinfunction "A7_7") (pintype "unspecified+no_connect"))
    )
    (net (code "137") (name "unconnected-(U1-A8-Pad8)") (class "Default")
      (node (ref "U1") (pin "8") (pinfunction "A8_8") (pintype "unspecified+no_connect"))
    )
    (net (code "138") (name "unconnected-(U1-A9-Pad9)") (class "Default")
      (node (ref "U1") (pin "9") (pinfunction "A9_9") (pintype "unspecified+no_connect"))
    )
    (net (code "139") (name "unconnected-(U1-A10-Pad10)") (class "Default")
      (node (ref "U1") (pin "10") (pinfunction "A10_10") (pintype "unspecified+no_connect"))
    )
    (net (code "140") (name "unconnected-(U1-A60-Pad60)") (class "Default")
      (node (ref "U1") (pin "60") (pinfunction "A60_60") (pintype "unspecified+no_connect"))
    )
    (net (code "141") (name "unconnected-(U1-A61-Pad61)") (class "Default")
      (node (ref "U1") (pin "61") (pinfunction "A61_61") (pintype "unspecified+no_connect"))
    )
    (net (code "142") (name "unconnected-(U1-A62-Pad62)") (class "Default")
      (node (ref "U1") (pin "62") (pinfunction "A62_62") (pintype "unspecified+no_connect"))
    )
    (net (code "143") (name "unconnected-(U1-A63-Pad63)") (class "Default")
      (node (ref "U1") (pin "63") (pinfunction "A63_63") (pintype "unspecified+no_connect"))
    )
    (net (code "144") (name "unconnected-(U1-A64-Pad64)") (class "Default")
      (node (ref "U1") (pin "64") (pinfunction "A64_64") (pintype "unspecified+no_connect"))
    )
    (net (code "145") (name "unconnected-(U1-A65-Pad65)") (class "Default")
      (node (ref "U1") (pin "65") (pinfunction "A65_65") (pintype "unspecified+no_connect"))
    )
    (net (code "146") (name "unconnected-(U1-B1-Pad66)") (class "Default")
      (node (ref "U1") (pin "66") (pinfunction "B1_66") (pintype "unspecified+no_connect"))
    )
    (net (code "147") (name "unconnected-(U1-B2-Pad67)") (class "Default")
      (node (ref "U1") (pin "67") (pinfunction "B2_67") (pintype "unspecified+no_connect"))
    )
    (net (code "148") (name "unconnected-(U1-B3-Pad68)") (class "Default")
      (node (ref "U1") (pin "68") (pinfunction "B3_68") (pintype "unspecified+no_connect"))
    )
    (net (code "149") (name "unconnected-(U1-B4-Pad69)") (class "Default")
      (node (ref "U1") (pin "69") (pinfunction "B4_69") (pintype "unspecified+no_connect"))
    )
    (net (code "150") (name "unconnected-(U1-B5-Pad70)") (class "Default")
      (node (ref "U1") (pin "70") (pinfunction "B5_70") (pintype "unspecified+no_connect"))
    )
    (net (code "151") (name "unconnected-(U1-B6-Pad71)") (class "Default")
      (node (ref "U1") (pin "71") (pinfunction "B6_71") (pintype "unspecified+no_connect"))
    )
    (net (code "152") (name "unconnected-(U1-B7-Pad72)") (class "Default")
      (node (ref "U1") (pin "72") (pinfunction "B7_72") (pintype "unspecified+no_connect"))
    )
    (net (code "153") (name "unconnected-(U1-B8-Pad73)") (class "Default")
      (node (ref "U1") (pin "73") (pinfunction "B8_73") (pintype "unspecified+no_connect"))
    )
    (net (code "154") (name "unconnected-(U1-B9-Pad74)") (class "Default")
      (node (ref "U1") (pin "74") (pinfunction "B9_74") (pintype "unspecified+no_connect"))
    )
    (net (code "155") (name "unconnected-(U1-B10-Pad75)") (class "Default")
      (node (ref "U1") (pin "75") (pinfunction "B10_75") (pintype "unspecified+no_connect"))
    )
    (net (code "156") (name "unconnected-(U1-B60-Pad125)") (class "Default")
      (node (ref "U1") (pin "125") (pinfunction "B60_125") (pintype "unspecified+no_connect"))
    )
    (net (code "157") (name "unconnected-(U1-B61-Pad126)") (class "Default")
      (node (ref "U1") (pin "126") (pinfunction "B61_126") (pintype "unspecified+no_connect"))
    )
    (net (code "158") (name "unconnected-(U1-B62-Pad127)") (class "Default")
      (node (ref "U1") (pin "127") (pinfunction "B62_127") (pintype "unspecified+no_connect"))
    )
    (net (code "159") (name "unconnected-(U1-B63-Pad128)") (class "Default")
      (node (ref "U1") (pin "128") (pinfunction "B63_128") (pintype "unspecified+no_connect"))
    )
    (net (code "160") (name "unconnected-(U1-B64-Pad129)") (class "Default")
      (node (ref "U1") (pin "129") (pinfunction "B64_129") (pintype "unspecified+no_connect"))
    )
    (net (code "161") (name "unconnected-(U1-B65-Pad130)") (class "Default")
      (node (ref "U1") (pin "130") (pinfunction "B65_130") (pintype "unspecified+no_connect"))
    )
    (net (code "162") (name "unconnected-(U1-C1-Pad131)") (class "Default")
      (node (ref "U1") (pin "131") (pinfunction "C1_131") (pintype "unspecified+no_connect"))
    )
    (net (code "163") (name "unconnected-(U1-C2-Pad132)") (class "Default")
      (node (ref "U1") (pin "132") (pinfunction "C2_132") (pintype "unspecified+no_connect"))
    )
    (net (code "164") (name "unconnected-(U1-C3-Pad133)") (class "Default")
      (node (ref "U1") (pin "133") (pinfunction "C3_133") (pintype "unspecified+no_connect"))
    )
    (net (code "165") (name "unconnected-(U1-C4-Pad134)") (class "Default")
      (node (ref "U1") (pin "134") (pinfunction "C4_134") (pintype "unspecified+no_connect"))
    )
    (net (code "166") (name "unconnected-(U1-C5-Pad135)") (class "Default")
      (node (ref "U1") (pin "135") (pinfunction "C5_135") (pintype "unspecified+no_connect"))
    )
    (net (code "167") (name "unconnected-(U1-C6-Pad136)") (class "Default")
      (node (ref "U1") (pin "136") (pinfunction "C6_136") (pintype "unspecified+no_connect"))
    )
    (net (code "168") (name "unconnected-(U1-C7-Pad137)") (class "Default")
      (node (ref "U1") (pin "137") (pinfunction "C7_137") (pintype "unspecified+no_connect"))
    )
    (net (code "169") (name "unconnected-(U1-C8-Pad138)") (class "Default")
      (node (ref "U1") (pin "138") (pinfunction "C8_138") (pintype "unspecified+no_connect"))
    )
    (net (code "170") (name "unconnected-(U1-C9-Pad139)") (class "Default")
      (node (ref "U1") (pin "139") (pinfunction "C9_139") (pintype "unspecified+no_connect"))
    )
    (net (code "171") (name "unconnected-(U1-C10-Pad140)") (class "Default")
      (node (ref "U1") (pin "140") (pinfunction "C10_140") (pintype "unspecified+no_connect"))
    )
    (net (code "172") (name "unconnected-(U1-C60-Pad190)") (class "Default")
      (node (ref "U1") (pin "190") (pinfunction "C60_190") (pintype "unspecified+no_connect"))
    )
    (net (code "173") (name "unconnected-(U1-C61-Pad191)") (class "Default")
      (node (ref "U1") (pin "191") (pinfunction "C61_191") (pintype "unspecified+no_connect"))
    )
    (net (code "174") (name "unconnected-(U1-C62-Pad192)") (class "Default")
      (node (ref "U1") (pin "192") (pinfunction "C62_192") (pintype "unspecified+no_connect"))
    )
    (net (code "175") (name "unconnected-(U1-C63-Pad193)") (class "Default")
      (node (ref "U1") (pin "193") (pinfunction "C63_193") (pintype "unspecified+no_connect"))
    )
    (net (code "176") (name "unconnected-(U1-C64-Pad194)") (class "Default")
      (node (ref "U1") (pin "194") (pinfunction "C64_194") (pintype "unspecified+no_connect"))
    )
    (net (code "177") (name "unconnected-(U1-C65-Pad195)") (class "Default")
      (node (ref "U1") (pin "195") (pinfunction "C65_195") (pintype "unspecified+no_connect"))
    )
    (net (code "178") (name "unconnected-(U1-D1-Pad196)") (class "Default")
      (node (ref "U1") (pin "196") (pinfunction "D1_196") (pintype "unspecified+no_connect"))
    )
    (net (code "179") (name "unconnected-(U1-D2-Pad197)") (class "Default")
      (node (ref "U1") (pin "197") (pinfunction "D2_197") (pintype "unspecified+no_connect"))
    )
    (net (code "180") (name "unconnected-(U1-D3-Pad198)") (class "Default")
      (node (ref "U1") (pin "198") (pinfunction "D3_198") (pintype "unspecified+no_connect"))
    )
    (net (code "181") (name "unconnected-(U1-D4-Pad199)") (class "Default")
      (node (ref "U1") (pin "199") (pinfunction "D4_199") (pintype "unspecified+no_connect"))
    )
    (net (code "182") (name "unconnected-(U1-D5-Pad200)") (class "Default")
      (node (ref "U1") (pin "200") (pinfunction "D5_200") (pintype "unspecified+no_connect"))
    )
    (net (code "183") (name "unconnected-(U1-D6-Pad201)") (class "Default")
      (node (ref "U1") (pin "201") (pinfunction "D6_201") (pintype "unspecified+no_connect"))
    )
    (net (code "184") (name "unconnected-(U1-D7-Pad202)") (class "Default")
      (node (ref "U1") (pin "202") (pinfunction "D7_202") (pintype "unspecified+no_connect"))
    )
    (net (code "185") (name "unconnected-(U1-D8-Pad203)") (class "Default")
      (node (ref "U1") (pin "203") (pinfunction "D8_203") (pintype "unspecified+no_connect"))
    )
    (net (code "186") (name "unconnected-(U1-D9-Pad204)") (class "Default")
      (node (ref "U1") (pin "204") (pinfunction "D9_204") (pintype "unspecified+no_connect"))
    )
    (net (code "187") (name "unconnected-(U1-D10-Pad205)") (class "Default")
      (node (ref "U1") (pin "205") (pinfunction "D10_205") (pintype "unspecified+no_connect"))
    )
    (net (code "188") (name "unconnected-(U1-D60-Pad255)") (class "Default")
      (node (ref "U1") (pin "255") (pinfunction "D60_255") (pintype "unspecified+no_connect"))
    )
    (net (code "189") (name "unconnected-(U1-D61-Pad256)") (class "Default")
      (node (ref "U1") (pin "256") (pinfunction "D61_256") (pintype "unspecified+no_connect"))
    )
    (net (code "190") (name "unconnected-(U1-D62-Pad257)") (class "Default")
      (node (ref "U1") (pin "257") (pinfunction "D62_257") (pintype "unspecified+no_connect"))
    )
    (net (code "191") (name "unconnected-(U1-D63-Pad258)") (class "Default")
      (node (ref "U1") (pin "258") (pinfunction "D63_258") (pintype "unspecified+no_connect"))
    )
    (net (code "192") (name "unconnected-(U1-D64-Pad259)") (class "Default")
      (node (ref "U1") (pin "259") (pinfunction "D64_259") (pintype "unspecified+no_connect"))
    )
    (net (code "193") (name "unconnected-(U1-D65-Pad260)") (class "Default")
      (node (ref "U1") (pin "260") (pinfunction "D65_260") (pintype "unspecified+no_connect"))
    )
  )
)
